# v2.net
KiCad netlist of a schematic drawn in Altium Designer
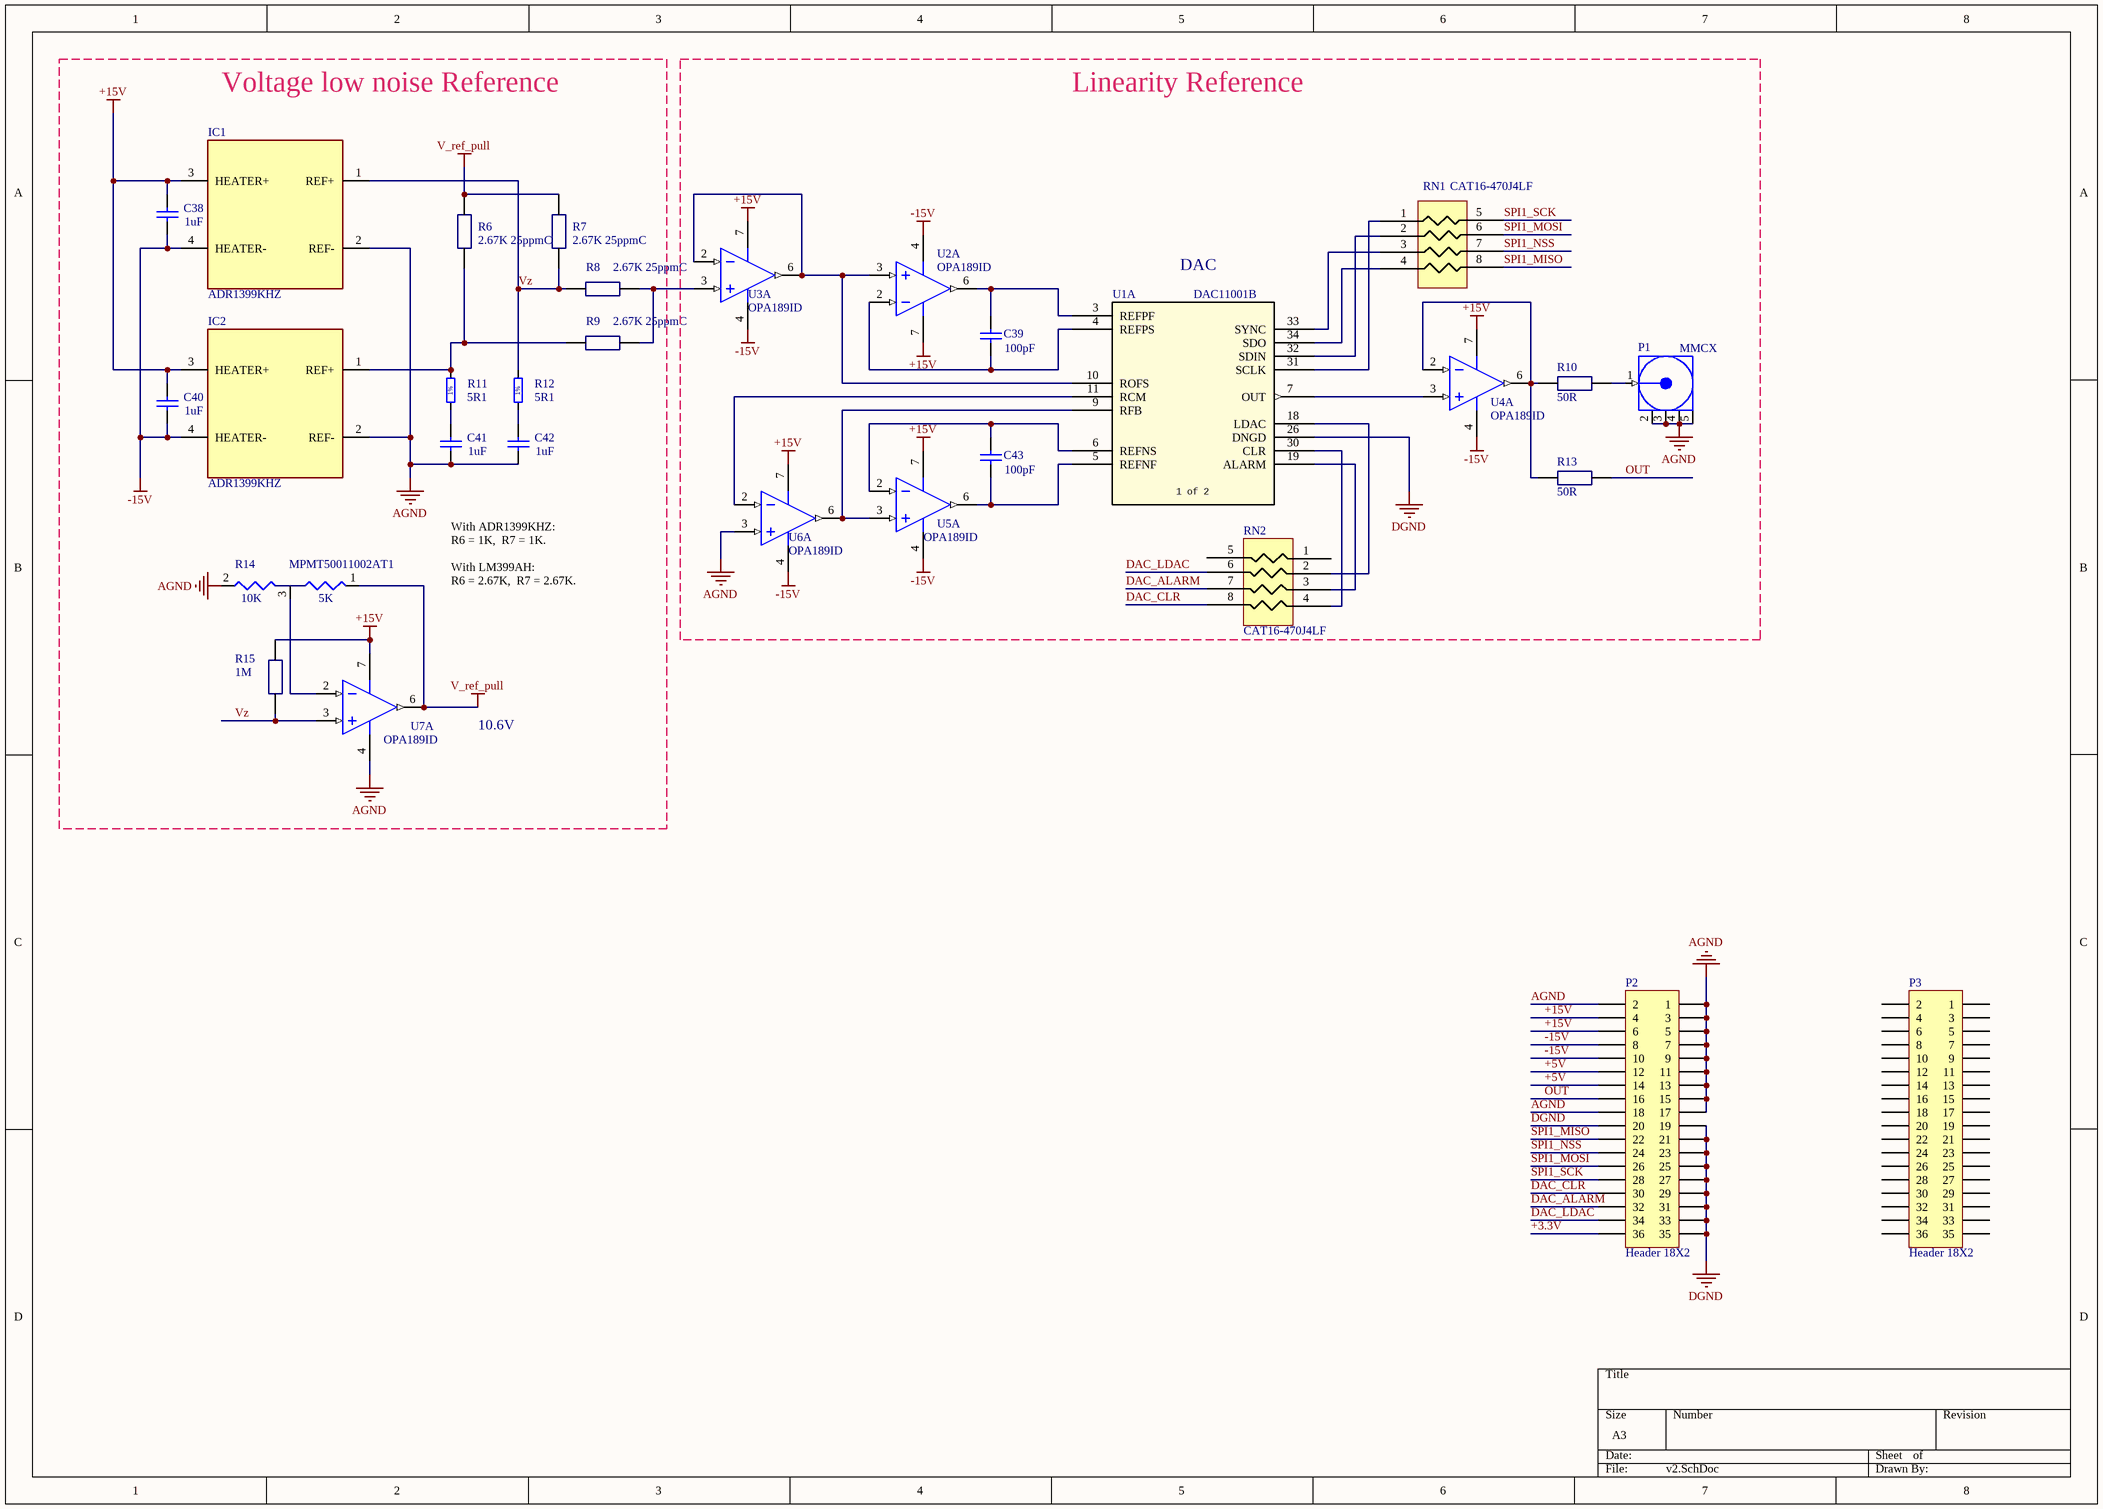
[diagram p0: v2.SchDoc]

(export (version "E")
  (design (tool "Eeschema 10.0.6"))
  (components
    (comp (ref "C38")
      (value "1uF")
      (footprint "CAPC3216X140N")
      (description "Non-polarised capacitor")
      (fields
        (field (name "PART NUMBER") "CC1206_1UF_25V_10%_X7R")
        (field (name "VOLTAGE") "25V")
        (field (name "AUTHOR") "CERN DEM JLC")
      )
      (libsource (lib "Capacitors") (part "Capacitor - non polarized"))
    )
    (comp (ref "C39")
      (value "100pF")
      (footprint "0402")
      (description "Capacitor (Semiconductor SIM Model)")
      (fields (field (name "Comment") "Cap Semi") (field (name "PUBLISHER") "Altium Limited"))
      (libsource (lib "Miscellaneous Devices") (part "Cap Semi"))
    )
    (comp (ref "C40")
      (value "1uF")
      (footprint "CAPC3216X140N")
      (description "Non-polarised capacitor")
      (fields
        (field (name "PART NUMBER") "CC1206_1UF_25V_10%_X7R")
        (field (name "VOLTAGE") "25V")
        (field (name "AUTHOR") "CERN DEM JLC")
      )
      (libsource (lib "Capacitors") (part "Capacitor - non polarized"))
    )
    (comp (ref "C41")
      (value "1uF")
      (footprint "CAPC3216X140N")
      (description "Non-polarised capacitor")
      (fields
        (field (name "PART NUMBER") "CC1206_1UF_25V_10%_X7R")
        (field (name "VOLTAGE") "25V")
        (field (name "AUTHOR") "CERN DEM JLC")
      )
      (libsource (lib "Capacitors") (part "Capacitor - non polarized"))
    )
    (comp (ref "C42")
      (value "1uF")
      (footprint "CAPC3216X140N")
      (description "Non-polarised capacitor")
      (fields
        (field (name "PART NUMBER") "CC1206_1UF_25V_10%_X7R")
        (field (name "VOLTAGE") "25V")
        (field (name "AUTHOR") "CERN DEM JLC")
      )
      (libsource (lib "Capacitors") (part "Capacitor - non polarized"))
    )
    (comp (ref "C43")
      (value "100pF")
      (footprint "0402")
      (description "Capacitor (Semiconductor SIM Model)")
      (fields (field (name "Comment") "Cap Semi") (field (name "PUBLISHER") "Altium Limited"))
      (libsource (lib "Miscellaneous Devices") (part "Cap Semi"))
    )
    (comp (ref "IC1")
      (value "ADR1399KHZ")
      (footprint "SamacSys:ADR1399KHZ")
      (description "Integrated Circuit")
      (libsource (lib "SamacSys") (part "ADR1399KHZ"))
    )
    (comp (ref "IC2")
      (value "ADR1399KHZ")
      (footprint "SamacSys:ADR1399KHZ")
      (description "Integrated Circuit")
      (libsource (lib "SamacSys") (part "ADR1399KHZ"))
    )
    (comp (ref "P1")
      (value "MMCX")
      (footprint "MMCX2.54-V5")
      (description "RF Coaxial PCB Connector, MMCX; Thru-Hole, Vertical Mount Plug,  50 Ohm Impedance")
      (fields (field (name "PUBLISHER") "Altium Limited"))
      (libsource (lib "Miscellaneous Connectors") (part "COAX-M"))
    )
    (comp (ref "P2")
      (value "Header 18X2")
      (footprint "HDR2X18")
      (description "Header, 18-Pin, Dual row")
      (fields (field (name "PUBLISHER") "Altium Limited"))
      (libsource (lib "Miscellaneous Connectors") (part "Header 18X2"))
    )
    (comp (ref "P3")
      (value "Header 18X2")
      (footprint "HDR2X18")
      (description "Header, 18-Pin, Dual row")
      (fields (field (name "PUBLISHER") "Altium Limited"))
      (libsource (lib "Miscellaneous Connectors") (part "Header 18X2"))
    )
    (comp (ref "R6")
      (value "2.67K 25ppmC")
      (footprint "1608[0603]")
      (libsource (lib "Микрон-3") (part "Resistor 0805"))
    )
    (comp (ref "R7")
      (value "2.67K 25ppmC")
      (footprint "1608[0603]")
      (libsource (lib "Микрон-3") (part "Resistor 0805"))
    )
    (comp (ref "R8")
      (value "2.67K 25ppmC")
      (footprint "1608[0603]")
      (libsource (lib "Микрон-3") (part "Resistor 0805"))
    )
    (comp (ref "R9")
      (value "2.67K 25ppmC")
      (footprint "1608[0603]")
      (libsource (lib "Микрон-3") (part "Resistor 0805"))
    )
    (comp (ref "R10")
      (value "50R")
      (footprint "1608[0603]")
      (libsource (lib "Микрон-3") (part "Resistor 0805"))
    )
    (comp (ref "R11")
      (value "5R1")
      (footprint "RESC3216X65N")
      (description "Resistor - 1%")
      (fields
        (field (name "PART NUMBER") "R1206_5R6_1%_0.25W_200PPM")
        (field (name "POWER") "0.25W")
        (field (name "AUTHOR") "CERN DEM JLC")
      )
      (libsource (lib "Resistors") (part "Resistor - 1%"))
    )
    (comp (ref "R12")
      (value "5R1")
      (footprint "RESC3216X65N")
      (description "Resistor - 1%")
      (fields
        (field (name "PART NUMBER") "R1206_5R6_1%_0.25W_200PPM")
        (field (name "POWER") "0.25W")
        (field (name "AUTHOR") "CERN DEM JLC")
      )
      (libsource (lib "Resistors") (part "Resistor - 1%"))
    )
    (comp (ref "R13")
      (value "50R")
      (footprint "1608[0603]")
      (libsource (lib "Микрон-3") (part "Resistor 0805"))
    )
    (comp (ref "R14")
      (value "5K")
      (footprint "SOT23-3")
      (fields
        (field (name "VALUE2") "10K")
        (field (name "ORDER") "MPMT50011002AT1")
        (field (name "Comment") "MPMT50011002AT1")
        (field (name "PUBLISHER") "Altium Limited")
      )
      (libsource (lib "My SCH library") (part "MPMT"))
    )
    (comp (ref "R15")
      (value "1M")
      (footprint "1608[0603]")
      (libsource (lib "Микрон-3") (part "Resistor 0805"))
    )
    (comp (ref "RN1")
      (value "CAT16-470J4LF")
      (footprint "CAT16-470J4LF")
      (libsource (lib "My SCH library") (part "CAT16-470J4LF"))
    )
    (comp (ref "RN2")
      (value "CAT16-470J4LF")
      (footprint "CAT16-470J4LF")
      (libsource (lib "") (part "CAT16-470J4LF_1"))
    )
    (comp (ref "U1")
      (value "DAC11001B")
      (footprint "QFP_APFBR_TEX")
      (description "No Description Available")
      (fields
        (field (name "MANUFACTURER_PART_NUMBER") "DAC11001APFBR")
        (field (name "COPYRIGHT") "Copyright (C) 2018 Accelerated Designs. All rights reserved")
      )
      (libsource (lib "Ramp-generator") (part "DAC11001APFBR"))
    )
    (comp (ref "U2")
      (value "OPA189ID")
      (footprint "TI-D8_L")
      (fields (field (name "MANUFACTURER") "Texas Instruments"))
      (libsource (lib "") (part "OPA140AIDR_1"))
    )
    (comp (ref "U3")
      (value "OPA189ID")
      (footprint "TI-D8_L")
      (fields (field (name "MANUFACTURER") "Texas Instruments"))
      (libsource (lib "TI Amplifiers and Linear Operational Amplifier Precision Amplifier Part One") (part "OPA140AIDR"))
    )
    (comp (ref "U4")
      (value "OPA189ID")
      (footprint "TI-D8_L")
      (fields (field (name "MANUFACTURER") "Texas Instruments"))
      (libsource (lib "TI Amplifiers and Linear Operational Amplifier Precision Amplifier Part One") (part "OPA140AIDR"))
    )
    (comp (ref "U5")
      (value "OPA189ID")
      (footprint "TI-D8_L")
      (fields (field (name "MANUFACTURER") "Texas Instruments"))
      (libsource (lib "TI Amplifiers and Linear Operational Amplifier Precision Amplifier Part One") (part "OPA140AIDR"))
    )
    (comp (ref "U6")
      (value "OPA189ID")
      (footprint "TI-D8_L")
      (fields (field (name "MANUFACTURER") "Texas Instruments"))
      (libsource (lib "TI Amplifiers and Linear Operational Amplifier Precision Amplifier Part One") (part "OPA140AIDR"))
    )
    (comp (ref "U7")
      (value "OPA189ID")
      (footprint "TI-D8_L")
      (fields (field (name "MANUFACTURER") "Texas Instruments"))
      (libsource (lib "TI Amplifiers and Linear Operational Amplifier Precision Amplifier Part One") (part "OPA140AIDR"))
    )
  )
  (nets
    (net (code "1") (name "+15V") (class "Default")
      (node (ref "C38") (pin "2") (pinfunction "2_2") (pintype "passive"))
      (node (ref "C40") (pin "2") (pinfunction "2_2") (pintype "passive"))
      (node (ref "IC1") (pin "3") (pinfunction "HEATER+_3") (pintype "passive"))
      (node (ref "IC2") (pin "3") (pinfunction "HEATER+_3") (pintype "passive"))
      (node (ref "P2") (pin "4") (pinfunction "4_4") (pintype "passive"))
      (node (ref "P2") (pin "6") (pinfunction "6_6") (pintype "passive"))
      (node (ref "R15") (pin "1") (pinfunction "A_1") (pintype "passive"))
      (node (ref "U2") (pin "7") (pinfunction "V+_7") (pintype "power_in"))
      (node (ref "U3") (pin "7") (pinfunction "V+_7") (pintype "power_in"))
      (node (ref "U4") (pin "7") (pinfunction "V+_7") (pintype "power_in"))
      (node (ref "U5") (pin "7") (pinfunction "V+_7") (pintype "power_in"))
      (node (ref "U6") (pin "7") (pinfunction "V+_7") (pintype "power_in"))
      (node (ref "U7") (pin "7") (pinfunction "V+_7") (pintype "power_in"))
    )
    (net (code "2") (name "-15V") (class "Default")
      (node (ref "C38") (pin "1") (pinfunction "1_1") (pintype "passive"))
      (node (ref "C40") (pin "1") (pinfunction "1_1") (pintype "passive"))
      (node (ref "IC1") (pin "4") (pinfunction "HEATER-_4") (pintype "passive"))
      (node (ref "IC2") (pin "4") (pinfunction "HEATER-_4") (pintype "passive"))
      (node (ref "P2") (pin "10") (pinfunction "10_10") (pintype "passive"))
      (node (ref "P2") (pin "8") (pinfunction "8_8") (pintype "passive"))
      (node (ref "U2") (pin "4") (pinfunction "V-_4") (pintype "power_in"))
      (node (ref "U3") (pin "4") (pinfunction "V-_4") (pintype "power_in"))
      (node (ref "U4") (pin "4") (pinfunction "V-_4") (pintype "power_in"))
      (node (ref "U5") (pin "4") (pinfunction "V-_4") (pintype "power_in"))
      (node (ref "U6") (pin "4") (pinfunction "V-_4") (pintype "power_in"))
    )
    (net (code "3") (name "/+3.3V") (class "Default")
      (node (ref "P2") (pin "36") (pinfunction "36_36") (pintype "passive"))
    )
    (net (code "4") (name "/+5V") (class "Default")
      (node (ref "P2") (pin "12") (pinfunction "12_12") (pintype "passive"))
      (node (ref "P2") (pin "14") (pinfunction "14_14") (pintype "passive"))
    )
    (net (code "5") (name "/DAC_ALARM") (class "Default")
      (node (ref "P2") (pin "32") (pinfunction "32_32") (pintype "passive"))
      (node (ref "RN2") (pin "7") (pinfunction "7_7") (pintype "passive"))
    )
    (net (code "6") (name "/DAC_CLR") (class "Default")
      (node (ref "P2") (pin "30") (pinfunction "30_30") (pintype "passive"))
      (node (ref "RN2") (pin "8") (pinfunction "8_8") (pintype "passive"))
    )
    (net (code "7") (name "/DAC_LDAC") (class "Default")
      (node (ref "P2") (pin "34") (pinfunction "34_34") (pintype "passive"))
      (node (ref "RN2") (pin "6") (pinfunction "6_6") (pintype "passive"))
    )
    (net (code "8") (name "/OUT") (class "Default")
      (node (ref "P2") (pin "16") (pinfunction "16_16") (pintype "passive"))
      (node (ref "R13") (pin "1") (pinfunction "A_1") (pintype "passive"))
    )
    (net (code "9") (name "/SPI1_MISO") (class "Default")
      (node (ref "P2") (pin "22") (pinfunction "22_22") (pintype "passive"))
      (node (ref "RN1") (pin "8") (pinfunction "8_8") (pintype "passive"))
    )
    (net (code "10") (name "/SPI1_MOSI") (class "Default")
      (node (ref "P2") (pin "26") (pinfunction "26_26") (pintype "passive"))
      (node (ref "RN1") (pin "6") (pinfunction "6_6") (pintype "passive"))
    )
    (net (code "11") (name "/SPI1_NSS") (class "Default")
      (node (ref "P2") (pin "24") (pinfunction "24_24") (pintype "passive"))
      (node (ref "RN1") (pin "7") (pinfunction "7_7") (pintype "passive"))
    )
    (net (code "12") (name "/SPI1_SCK") (class "Default")
      (node (ref "P2") (pin "28") (pinfunction "28_28") (pintype "passive"))
      (node (ref "RN1") (pin "5") (pinfunction "5_5") (pintype "passive"))
    )
    (net (code "13") (name "/Vz") (class "Default")
      (node (ref "IC1") (pin "1") (pinfunction "REF+_1") (pintype "passive"))
      (node (ref "R12") (pin "2") (pinfunction "2_2") (pintype "passive"))
      (node (ref "R15") (pin "2") (pinfunction "2_2") (pintype "passive"))
      (node (ref "R7") (pin "2") (pinfunction "2_2") (pintype "passive"))
      (node (ref "R8") (pin "2") (pinfunction "2_2") (pintype "passive"))
      (node (ref "U7") (pin "3") (pinfunction "IN+_3") (pintype "input"))
    )
    (net (code "14") (name "AGND") (class "Default")
      (node (ref "C41") (pin "1") (pinfunction "1_1") (pintype "passive"))
      (node (ref "C42") (pin "1") (pinfunction "1_1") (pintype "passive"))
      (node (ref "IC1") (pin "2") (pinfunction "REF-_2") (pintype "passive"))
      (node (ref "IC2") (pin "2") (pinfunction "REF-_2") (pintype "passive"))
      (node (ref "P1") (pin "2") (pinfunction "GND_2") (pintype "power_in"))
      (node (ref "P1") (pin "3") (pinfunction "GND_3") (pintype "power_in"))
      (node (ref "P1") (pin "4") (pinfunction "GND_4") (pintype "power_in"))
      (node (ref "P1") (pin "5") (pinfunction "GND_5") (pintype "power_in"))
      (node (ref "P2") (pin "1") (pinfunction "1_1") (pintype "passive"))
      (node (ref "P2") (pin "11") (pinfunction "11_11") (pintype "passive"))
      (node (ref "P2") (pin "13") (pinfunction "13_13") (pintype "passive"))
      (node (ref "P2") (pin "15") (pinfunction "15_15") (pintype "passive"))
      (node (ref "P2") (pin "17") (pinfunction "17_17") (pintype "passive"))
      (node (ref "P2") (pin "18") (pinfunction "18_18") (pintype "passive"))
      (node (ref "P2") (pin "2") (pinfunction "2_2") (pintype "passive"))
      (node (ref "P2") (pin "3") (pinfunction "3_3") (pintype "passive"))
      (node (ref "P2") (pin "5") (pinfunction "5_5") (pintype "passive"))
      (node (ref "P2") (pin "7") (pinfunction "7_7") (pintype "passive"))
      (node (ref "P2") (pin "9") (pinfunction "9_9") (pintype "passive"))
      (node (ref "R14") (pin "2") (pinfunction "2_2") (pintype "passive"))
      (node (ref "U6") (pin "3") (pinfunction "IN+_3") (pintype "input"))
      (node (ref "U7") (pin "4") (pinfunction "V-_4") (pintype "power_in"))
    )
    (net (code "15") (name "DGND") (class "Default")
      (node (ref "P2") (pin "19") (pinfunction "19_19") (pintype "passive"))
      (node (ref "P2") (pin "20") (pinfunction "20_20") (pintype "passive"))
      (node (ref "P2") (pin "21") (pinfunction "21_21") (pintype "passive"))
      (node (ref "P2") (pin "23") (pinfunction "23_23") (pintype "passive"))
      (node (ref "P2") (pin "25") (pinfunction "25_25") (pintype "passive"))
      (node (ref "P2") (pin "27") (pinfunction "27_27") (pintype "passive"))
      (node (ref "P2") (pin "29") (pinfunction "29_29") (pintype "passive"))
      (node (ref "P2") (pin "31") (pinfunction "31_31") (pintype "passive"))
      (node (ref "P2") (pin "33") (pinfunction "33_33") (pintype "passive"))
      (node (ref "P2") (pin "35") (pinfunction "35_35") (pintype "passive"))
      (node (ref "U1") (pin "26") (pinfunction "DNGD_26") (pintype "passive"))
    )
    (net (code "16") (name "Net-(C41-Pad2)") (class "Default")
      (node (ref "C41") (pin "2") (pinfunction "2_2") (pintype "passive"))
      (node (ref "R11") (pin "1") (pinfunction "1_1") (pintype "passive"))
    )
    (net (code "17") (name "Net-(C42-Pad2)") (class "Default")
      (node (ref "C42") (pin "2") (pinfunction "2_2") (pintype "passive"))
      (node (ref "R12") (pin "1") (pinfunction "1_1") (pintype "passive"))
    )
    (net (code "18") (name "Net-(IC2-REF+)") (class "Default")
      (node (ref "IC2") (pin "1") (pinfunction "REF+_1") (pintype "passive"))
      (node (ref "R11") (pin "2") (pinfunction "2_2") (pintype "passive"))
      (node (ref "R6") (pin "2") (pinfunction "2_2") (pintype "passive"))
      (node (ref "R9") (pin "2") (pinfunction "2_2") (pintype "passive"))
    )
    (net (code "19") (name "Net-(P1-Signal)") (class "Default")
      (node (ref "P1") (pin "1") (pinfunction "Signal_1") (pintype "input"))
      (node (ref "R10") (pin "1") (pinfunction "A_1") (pintype "passive"))
    )
    (net (code "20") (name "Net-(R8-A)") (class "Default")
      (node (ref "R8") (pin "1") (pinfunction "A_1") (pintype "passive"))
      (node (ref "R9") (pin "1") (pinfunction "A_1") (pintype "passive"))
      (node (ref "U3") (pin "3") (pinfunction "IN+_3") (pintype "input"))
    )
    (net (code "21") (name "Net-(U1A-ALARM)") (class "Default")
      (node (ref "RN2") (pin "3") (pinfunction "3_3") (pintype "passive"))
      (node (ref "U1") (pin "19") (pinfunction "ALARM_19") (pintype "passive"))
    )
    (net (code "22") (name "Net-(U1A-CLR)") (class "Default")
      (node (ref "RN2") (pin "4") (pinfunction "4_4") (pintype "passive"))
      (node (ref "U1") (pin "30") (pinfunction "CLR_30") (pintype "passive"))
    )
    (net (code "23") (name "Net-(U1A-LDAC)") (class "Default")
      (node (ref "RN2") (pin "2") (pinfunction "2_2") (pintype "passive"))
      (node (ref "U1") (pin "18") (pinfunction "LDAC_18") (pintype "passive"))
    )
    (net (code "24") (name "Net-(U1A-OUT)") (class "Default")
      (node (ref "U1") (pin "7") (pinfunction "OUT_7") (pintype "output"))
      (node (ref "U4") (pin "3") (pinfunction "IN+_3") (pintype "input"))
    )
    (net (code "25") (name "Net-(U1A-RCM)") (class "Default")
      (node (ref "U1") (pin "11") (pinfunction "RCM_11") (pintype "passive"))
      (node (ref "U6") (pin "2") (pinfunction "IN-_2") (pintype "input"))
    )
    (net (code "26") (name "Net-(U1A-REFNF)") (class "Default")
      (node (ref "C43") (pin "1") (pinfunction "1_1") (pintype "passive"))
      (node (ref "U1") (pin "5") (pinfunction "REFNF_5") (pintype "passive"))
      (node (ref "U5") (pin "6") (pinfunction "OUT_6") (pintype "output"))
    )
    (net (code "27") (name "Net-(U1A-REFNS)") (class "Default")
      (node (ref "C43") (pin "2") (pinfunction "2_2") (pintype "passive"))
      (node (ref "U1") (pin "6") (pinfunction "REFNS_6") (pintype "passive"))
      (node (ref "U5") (pin "2") (pinfunction "IN-_2") (pintype "input"))
    )
    (net (code "28") (name "Net-(U1A-REFPF)") (class "Default")
      (node (ref "C39") (pin "2") (pinfunction "2_2") (pintype "passive"))
      (node (ref "U1") (pin "3") (pinfunction "REFPF_3") (pintype "passive"))
      (node (ref "U2") (pin "6") (pinfunction "OUT_6") (pintype "output"))
    )
    (net (code "29") (name "Net-(U1A-REFPS)") (class "Default")
      (node (ref "C39") (pin "1") (pinfunction "1_1") (pintype "passive"))
      (node (ref "U1") (pin "4") (pinfunction "REFPS_4") (pintype "passive"))
      (node (ref "U2") (pin "2") (pinfunction "IN-_2") (pintype "input"))
    )
    (net (code "30") (name "Net-(U1A-RFB)") (class "Default")
      (node (ref "U1") (pin "9") (pinfunction "RFB_9") (pintype "passive"))
      (node (ref "U5") (pin "3") (pinfunction "IN+_3") (pintype "input"))
      (node (ref "U6") (pin "6") (pinfunction "OUT_6") (pintype "output"))
    )
    (net (code "31") (name "Net-(U1A-ROFS)") (class "Default")
      (node (ref "U1") (pin "10") (pinfunction "ROFS_10") (pintype "passive"))
      (node (ref "U2") (pin "3") (pinfunction "IN+_3") (pintype "input"))
      (node (ref "U3") (pin "2") (pinfunction "IN-_2") (pintype "input"))
      (node (ref "U3") (pin "6") (pinfunction "OUT_6") (pintype "output"))
    )
    (net (code "32") (name "Net-(U1A-SCLK)") (class "Default")
      (node (ref "RN1") (pin "1") (pinfunction "1_1") (pintype "passive"))
      (node (ref "U1") (pin "31") (pinfunction "SCLK_31") (pintype "passive"))
    )
    (net (code "33") (name "Net-(U1A-SDIN)") (class "Default")
      (node (ref "RN1") (pin "2") (pinfunction "2_2") (pintype "passive"))
      (node (ref "U1") (pin "32") (pinfunction "SDIN_32") (pintype "passive"))
    )
    (net (code "34") (name "Net-(U1A-SDO)") (class "Default")
      (node (ref "RN1") (pin "4") (pinfunction "4_4") (pintype "passive"))
      (node (ref "U1") (pin "34") (pinfunction "SDO_34") (pintype "passive"))
    )
    (net (code "35") (name "Net-(U1A-SYNC)") (class "Default")
      (node (ref "RN1") (pin "3") (pinfunction "3_3") (pintype "passive"))
      (node (ref "U1") (pin "33") (pinfunction "SYNC_33") (pintype "passive"))
    )
    (net (code "36") (name "Net-(U4A-IN-)") (class "Default")
      (node (ref "R10") (pin "2") (pinfunction "2_2") (pintype "passive"))
      (node (ref "R13") (pin "2") (pinfunction "2_2") (pintype "passive"))
      (node (ref "U4") (pin "2") (pinfunction "IN-_2") (pintype "input"))
      (node (ref "U4") (pin "6") (pinfunction "OUT_6") (pintype "output"))
    )
    (net (code "37") (name "Net-(U7A-IN-)") (class "Default")
      (node (ref "R14") (pin "3") (pinfunction "3_3") (pintype "passive"))
      (node (ref "U7") (pin "2") (pinfunction "IN-_2") (pintype "input"))
    )
    (net (code "38") (name "V_ref_pull") (class "Default")
      (node (ref "R14") (pin "1") (pinfunction "1_1") (pintype "passive"))
      (node (ref "R6") (pin "1") (pinfunction "A_1") (pintype "passive"))
      (node (ref "R7") (pin "1") (pinfunction "A_1") (pintype "passive"))
      (node (ref "U7") (pin "6") (pinfunction "OUT_6") (pintype "output"))
    )
    (net (code "39") (name "unconnected-(P3-Pad1)") (class "Default")
      (node (ref "P3") (pin "1") (pinfunction "1_1") (pintype "passive"))
    )
    (net (code "40") (name "unconnected-(P3-Pad2)") (class "Default")
      (node (ref "P3") (pin "2") (pinfunction "2_2") (pintype "passive"))
    )
    (net (code "41") (name "unconnected-(P3-Pad3)") (class "Default")
      (node (ref "P3") (pin "3") (pinfunction "3_3") (pintype "passive"))
    )
    (net (code "42") (name "unconnected-(P3-Pad4)") (class "Default")
      (node (ref "P3") (pin "4") (pinfunction "4_4") (pintype "passive"))
    )
    (net (code "43") (name "unconnected-(P3-Pad5)") (class "Default")
      (node (ref "P3") (pin "5") (pinfunction "5_5") (pintype "passive"))
    )
    (net (code "44") (name "unconnected-(P3-Pad6)") (class "Default")
      (node (ref "P3") (pin "6") (pinfunction "6_6") (pintype "passive"))
    )
    (net (code "45") (name "unconnected-(P3-Pad7)") (class "Default")
      (node (ref "P3") (pin "7") (pinfunction "7_7") (pintype "passive"))
    )
    (net (code "46") (name "unconnected-(P3-Pad8)") (class "Default")
      (node (ref "P3") (pin "8") (pinfunction "8_8") (pintype "passive"))
    )
    (net (code "47") (name "unconnected-(P3-Pad9)") (class "Default")
      (node (ref "P3") (pin "9") (pinfunction "9_9") (pintype "passive"))
    )
    (net (code "48") (name "unconnected-(P3-Pad10)") (class "Default")
      (node (ref "P3") (pin "10") (pinfunction "10_10") (pintype "passive"))
    )
    (net (code "49") (name "unconnected-(P3-Pad11)") (class "Default")
      (node (ref "P3") (pin "11") (pinfunction "11_11") (pintype "passive"))
    )
    (net (code "50") (name "unconnected-(P3-Pad12)") (class "Default")
      (node (ref "P3") (pin "12") (pinfunction "12_12") (pintype "passive"))
    )
    (net (code "51") (name "unconnected-(P3-Pad13)") (class "Default")
      (node (ref "P3") (pin "13") (pinfunction "13_13") (pintype "passive"))
    )
    (net (code "52") (name "unconnected-(P3-Pad14)") (class "Default")
      (node (ref "P3") (pin "14") (pinfunction "14_14") (pintype "passive"))
    )
    (net (code "53") (name "unconnected-(P3-Pad15)") (class "Default")
      (node (ref "P3") (pin "15") (pinfunction "15_15") (pintype "passive"))
    )
    (net (code "54") (name "unconnected-(P3-Pad16)") (class "Default")
      (node (ref "P3") (pin "16") (pinfunction "16_16") (pintype "passive"))
    )
    (net (code "55") (name "unconnected-(P3-Pad17)") (class "Default")
      (node (ref "P3") (pin "17") (pinfunction "17_17") (pintype "passive"))
    )
    (net (code "56") (name "unconnected-(P3-Pad18)") (class "Default")
      (node (ref "P3") (pin "18") (pinfunction "18_18") (pintype "passive"))
    )
    (net (code "57") (name "unconnected-(P3-Pad19)") (class "Default")
      (node (ref "P3") (pin "19") (pinfunction "19_19") (pintype "passive"))
    )
    (net (code "58") (name "unconnected-(P3-Pad20)") (class "Default")
      (node (ref "P3") (pin "20") (pinfunction "20_20") (pintype "passive"))
    )
    (net (code "59") (name "unconnected-(P3-Pad21)") (class "Default")
      (node (ref "P3") (pin "21") (pinfunction "21_21") (pintype "passive"))
    )
    (net (code "60") (name "unconnected-(P3-Pad22)") (class "Default")
      (node (ref "P3") (pin "22") (pinfunction "22_22") (pintype "passive"))
    )
    (net (code "61") (name "unconnected-(P3-Pad23)") (class "Default")
      (node (ref "P3") (pin "23") (pinfunction "23_23") (pintype "passive"))
    )
    (net (code "62") (name "unconnected-(P3-Pad24)") (class "Default")
      (node (ref "P3") (pin "24") (pinfunction "24_24") (pintype "passive"))
    )
    (net (code "63") (name "unconnected-(P3-Pad25)") (class "Default")
      (node (ref "P3") (pin "25") (pinfunction "25_25") (pintype "passive"))
    )
    (net (code "64") (name "unconnected-(P3-Pad26)") (class "Default")
      (node (ref "P3") (pin "26") (pinfunction "26_26") (pintype "passive"))
    )
    (net (code "65") (name "unconnected-(P3-Pad27)") (class "Default")
      (node (ref "P3") (pin "27") (pinfunction "27_27") (pintype "passive"))
    )
    (net (code "66") (name "unconnected-(P3-Pad28)") (class "Default")
      (node (ref "P3") (pin "28") (pinfunction "28_28") (pintype "passive"))
    )
    (net (code "67") (name "unconnected-(P3-Pad29)") (class "Default")
      (node (ref "P3") (pin "29") (pinfunction "29_29") (pintype "passive"))
    )
    (net (code "68") (name "unconnected-(P3-Pad30)") (class "Default")
      (node (ref "P3") (pin "30") (pinfunction "30_30") (pintype "passive"))
    )
    (net (code "69") (name "unconnected-(P3-Pad31)") (class "Default")
      (node (ref "P3") (pin "31") (pinfunction "31_31") (pintype "passive"))
    )
    (net (code "70") (name "unconnected-(P3-Pad32)") (class "Default")
      (node (ref "P3") (pin "32") (pinfunction "32_32") (pintype "passive"))
    )
    (net (code "71") (name "unconnected-(P3-Pad33)") (class "Default")
      (node (ref "P3") (pin "33") (pinfunction "33_33") (pintype "passive"))
    )
    (net (code "72") (name "unconnected-(P3-Pad34)") (class "Default")
      (node (ref "P3") (pin "34") (pinfunction "34_34") (pintype "passive"))
    )
    (net (code "73") (name "unconnected-(P3-Pad35)") (class "Default")
      (node (ref "P3") (pin "35") (pinfunction "35_35") (pintype "passive"))
    )
    (net (code "74") (name "unconnected-(P3-Pad36)") (class "Default")
      (node (ref "P3") (pin "36") (pinfunction "36_36") (pintype "passive"))
    )
    (net (code "75") (name "unconnected-(RN2-Pad1)") (class "Default")
      (node (ref "RN2") (pin "1") (pinfunction "1_1") (pintype "passive"))
    )
    (net (code "76") (name "unconnected-(RN2-Pad5)") (class "Default")
      (node (ref "RN2") (pin "5") (pinfunction "5_5") (pintype "passive"))
    )
  )
)
